# TOP.net
KiCad netlist of a schematic drawn in Altium Designer
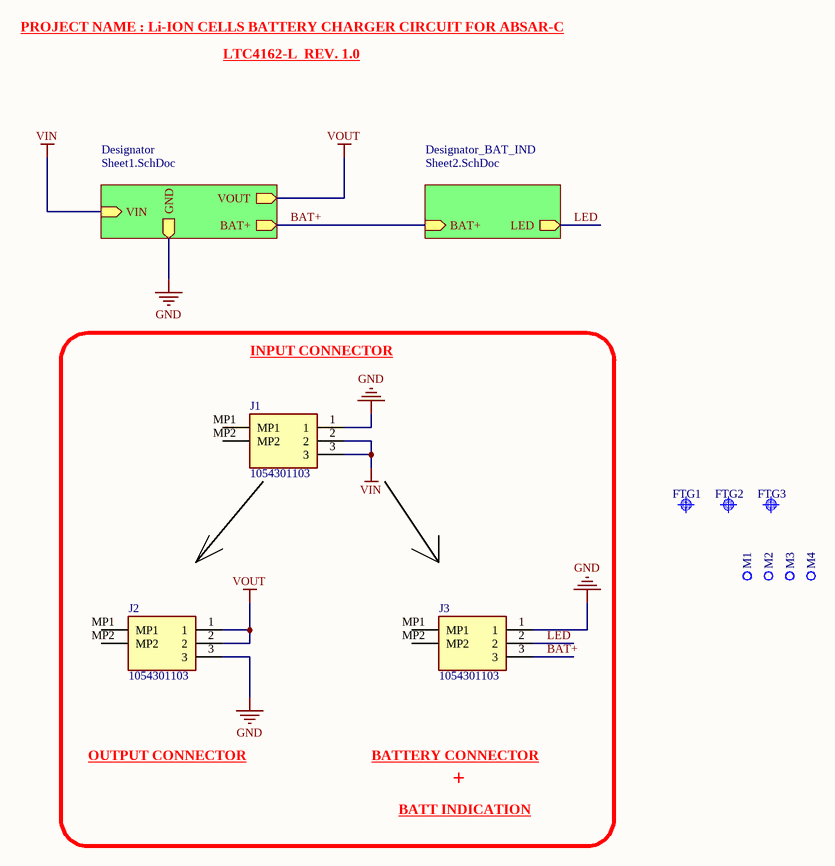
[diagram p0: TOP.SchDoc]

(export (version "E")
  (design (tool "Eeschema 10.0.6"))
  (components
    (comp (ref "FTG1")
      (value "Use only in PCB")
      (footprint "Fudicial")
      (description "Fiducial Target")
      (libsource (lib "Pads") (part "Fiducial Target"))
    )
    (comp (ref "FTG2")
      (value "Use only in PCB")
      (footprint "Fudicial")
      (description "Fiducial Target")
      (libsource (lib "Pads") (part "Fiducial Target"))
    )
    (comp (ref "FTG3")
      (value "Use only in PCB")
      (footprint "Fudicial")
      (description "Fiducial Target")
      (libsource (lib "Pads") (part "Fiducial Target"))
    )
    (comp (ref "J1")
      (value "1054301103")
      (footprint "SamacSys:1054301103")
      (description "Connector")
      (libsource (lib "*") (part "1054301103"))
    )
    (comp (ref "J2")
      (value "1054301103")
      (footprint "SamacSys:1054301103")
      (description "Connector")
      (libsource (lib "*") (part "1054301103"))
    )
    (comp (ref "J3")
      (value "1054301103")
      (footprint "SamacSys:1054301103")
      (description "Connector")
      (libsource (lib "*") (part "1054301103"))
    )
    (comp (ref "M1")
      (value "~")
      (footprint "Mounting_pad")
      (description "Through Hole Pad")
      (libsource (lib "Pads") (part "Through Hole Pad"))
    )
    (comp (ref "M2")
      (value "~")
      (footprint "Mounting_pad")
      (description "Through Hole Pad")
      (libsource (lib "Pads") (part "Through Hole Pad"))
    )
    (comp (ref "M3")
      (value "~")
      (footprint "Mounting_pad")
      (description "Through Hole Pad")
      (libsource (lib "Pads") (part "Through Hole Pad"))
    )
    (comp (ref "M4")
      (value "~")
      (footprint "Mounting_pad")
      (description "Through Hole Pad")
      (libsource (lib "Pads") (part "Through Hole Pad"))
    )
  )
  (nets
    (net (code "1") (name "/BAT+") (class "Default")
      (node (ref "J3") (pin "3") (pinfunction "3_3") (pintype "passive"))
    )
    (net (code "2") (name "/LED") (class "Default")
      (node (ref "J3") (pin "2") (pinfunction "2_2") (pintype "passive"))
    )
    (net (code "3") (name "GND") (class "Default")
      (node (ref "J1") (pin "1") (pinfunction "1_1") (pintype "passive"))
      (node (ref "J2") (pin "3") (pinfunction "3_3") (pintype "passive"))
      (node (ref "J3") (pin "1") (pinfunction "1_1") (pintype "passive"))
    )
    (net (code "4") (name "VIN") (class "Default")
      (node (ref "J1") (pin "2") (pinfunction "2_2") (pintype "passive"))
      (node (ref "J1") (pin "3") (pinfunction "3_3") (pintype "passive"))
    )
    (net (code "5") (name "VOUT") (class "Default")
      (node (ref "J2") (pin "1") (pinfunction "1_1") (pintype "passive"))
      (node (ref "J2") (pin "2") (pinfunction "2_2") (pintype "passive"))
    )
    (net (code "6") (name "unconnected-(J1-PadMP1)") (class "Default")
      (node (ref "J1") (pin "MP1") (pinfunction "MP1_MP1") (pintype "passive"))
    )
    (net (code "7") (name "unconnected-(J1-PadMP2)") (class "Default")
      (node (ref "J1") (pin "MP2") (pinfunction "MP2_MP2") (pintype "passive"))
    )
    (net (code "8") (name "unconnected-(J2-PadMP1)") (class "Default")
      (node (ref "J2") (pin "MP1") (pinfunction "MP1_MP1") (pintype "passive"))
    )
    (net (code "9") (name "unconnected-(J2-PadMP2)") (class "Default")
      (node (ref "J2") (pin "MP2") (pinfunction "MP2_MP2") (pintype "passive"))
    )
    (net (code "10") (name "unconnected-(J3-PadMP1)") (class "Default")
      (node (ref "J3") (pin "MP1") (pinfunction "MP1_MP1") (pintype "passive"))
    )
    (net (code "11") (name "unconnected-(J3-PadMP2)") (class "Default")
      (node (ref "J3") (pin "MP2") (pinfunction "MP2_MP2") (pintype "passive"))
    )
    (net (code "12") (name "unconnected-(M1-Pad1)") (class "Default")
      (node (ref "M1") (pin "1") (pinfunction "1_1") (pintype "bidirectional"))
    )
    (net (code "13") (name "unconnected-(M2-Pad1)") (class "Default")
      (node (ref "M2") (pin "1") (pinfunction "1_1") (pintype "bidirectional"))
    )
    (net (code "14") (name "unconnected-(M3-Pad1)") (class "Default")
      (node (ref "M3") (pin "1") (pinfunction "1_1") (pintype "bidirectional"))
    )
    (net (code "15") (name "unconnected-(M4-Pad1)") (class "Default")
      (node (ref "M4") (pin "1") (pinfunction "1_1") (pintype "bidirectional"))
    )
  )
)
